# ShutdownLoop.net
KiCad netlist of a schematic drawn in Altium Designer
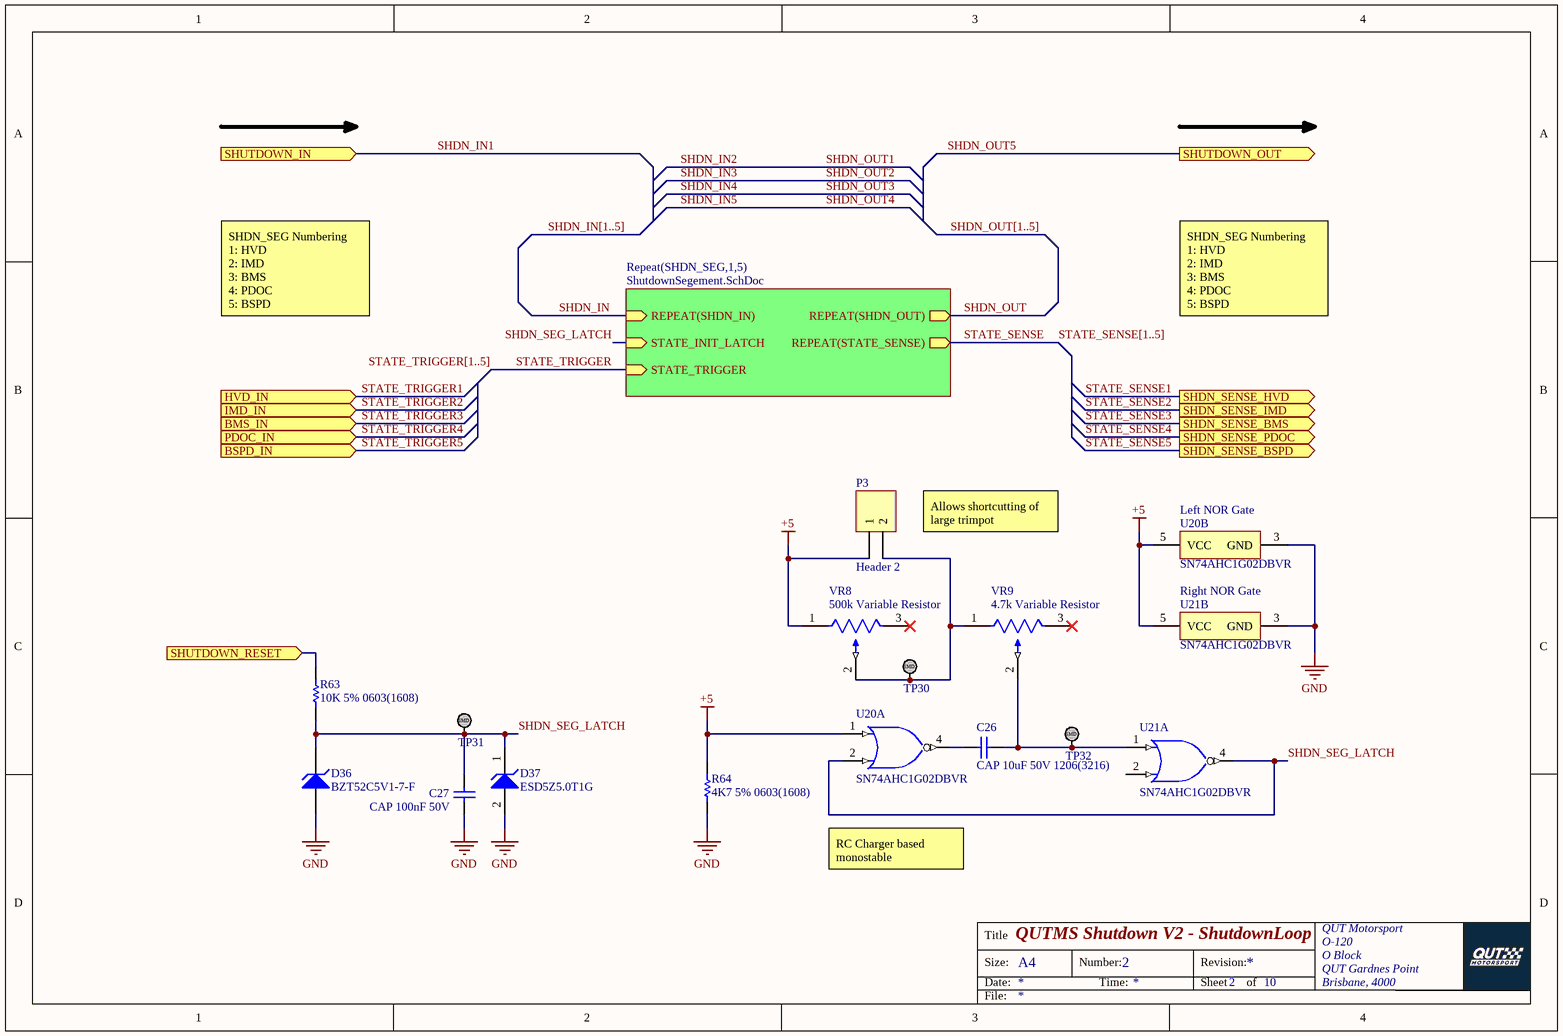
[diagram p0: ShutdownLoop.SchDoc]

(export (version "E")
  (design (tool "Eeschema 10.0.6"))
  (components
    (comp (ref "C26")
      (value "CAP 10uF 50V 1206(3216)")
      (footprint "CAPC1206(3216)190_M")
      (description "CAP 10uF 50V ±10% 1206 (3216 Metric) Thickness 1.9mm SMD")
      (fields (field (name "TOLERANCE") "Â±10%"))
      (libsource (lib "Altium Content Vault") (part "CAP"))
    )
    (comp (ref "C27")
      (value "CAP 100nF 50V")
      (footprint "CAPC0603(1608)100_L")
      (description "CAP 100nF 50V ±5% 0603 (1608 Metric) Thickness 1mm SMD")
      (fields (field (name "TOLERANCE") "Â±5%"))
      (libsource (lib "Altium Content Vault") (part "CAP"))
    )
    (comp (ref "D36")
      (value "BZT52C5V1-7-F")
      (footprint "DIOD-SOD123_V")
      (description "Surface Mount Zener Diode, 5.1 V, -65 to 150 degC, 2-Pin SMD (SOD-123), RoHS, Tape and Reel")
      (fields (field (name "MANUFACTURER") "DiodesIncorporated"))
      (libsource (lib "Altium Content Vault") (part "DZEN-AK-2"))
    )
    (comp (ref "D37")
      (value "ESD5Z5.0T1G")
      (footprint "ONSC-SOD-523-2-502-01_V")
      (fields (field (name "MANUFACTURER") "On Semiconductor"))
      (libsource (lib "Altium Content Vault") (part "ONSC-K1A2-2"))
    )
    (comp (ref "P3")
      (value "Header 2")
      (footprint "HDR1X2")
      (description "Header, 2-Pin")
      (fields (field (name "PUBLISHER") "Altium Limited"))
      (libsource (lib "Miscellaneous Connectors") (part "Header 2"))
    )
    (comp (ref "R63")
      (value "10K 5% 0603(1608)")
      (footprint "RESC0603(1608)_N")
      (description "10K 0.1W 5% 0603 (1608 Metric)  SMD")
      (fields (field (name "TOLERANCE") "5 %") (field (name "POWER") "0.1 W"))
      (libsource (lib "Altium Content Vault") (part "RES"))
    )
    (comp (ref "R64")
      (value "4K7 5% 0603(1608)")
      (footprint "RESC0603(1608)_N")
      (description "4K7 0.1W 5% 0603 (1608 Metric)  SMD")
      (fields (field (name "TOLERANCE") "5 %") (field (name "POWER") "0.1 W"))
      (libsource (lib "Altium Content Vault") (part "RES"))
    )
    (comp (ref "TP30")
      (value "TestPoint_SMD")
      (footprint "TestPointSMD")
      (libsource (lib "StandardTest") (part "TestPoint_SMD"))
    )
    (comp (ref "TP31")
      (value "TestPoint_SMD")
      (footprint "TestPointSMD")
      (libsource (lib "StandardTest") (part "TestPoint_SMD"))
    )
    (comp (ref "TP32")
      (value "TestPoint_SMD")
      (footprint "TestPointSMD")
      (libsource (lib "StandardTest") (part "TestPoint_SMD"))
    )
    (comp (ref "U20")
      (value "SN74AHC1G02DBVR")
      (footprint "DBV0005A_L")
      (description "Single 2-Input Positive-NOR Gate, DBV0005A, LARGE T&R")
      (fields
        (field (name "MANUFACTURER") "Texas Instruments")
        (field (name "GENERIC PART NUMBER") "SN74AHC1G02")
      )
      (libsource (lib "Altium Content Vault") (part "TI-SN74XXX1X02-5"))
    )
    (comp (ref "U21")
      (value "SN74AHC1G02DBVR")
      (footprint "DBV0005A_L")
      (description "Single 2-Input Positive-NOR Gate, DBV0005A, LARGE T&R")
      (fields
        (field (name "MANUFACTURER") "Texas Instruments")
        (field (name "GENERIC PART NUMBER") "SN74AHC1G02")
      )
      (libsource (lib "Altium Content Vault") (part "TI-SN74XXX1X02-5"))
    )
    (comp (ref "VR8")
      (value "500k Variable Resistor")
      (footprint "VG039NCHXTB472")
      (description "500K ±25% ±250 ppm/°C SMD Variable Resistors RoHS ¦ VG039NCHXTB504")
      (libsource (lib "QUTMS_PotentiometerLibrary") (part "500k Variable Resistor"))
    )
    (comp (ref "VR9")
      (value "4.7k Variable Resistor")
      (footprint "VG039NCHXTB472")
      (description "4k7 ±25% ±250 ppm/°C SMD Variable Resistors RoHS ¦ VG039NCHXTB472")
      (libsource (lib "QUTMS_PotentiometerLibrary") (part "4.7k Variable Resistor"))
    )
  )
  (nets
    (net (code "1") (name "+5") (class "Default")
      (node (ref "P3") (pin "1") (pinfunction "1_1") (pintype "passive"))
      (node (ref "R64") (pin "2") (pinfunction "2_2") (pintype "passive"))
      (node (ref "U20") (pin "1") (pinfunction "A_1") (pintype "input"))
      (node (ref "U20") (pin "5") (pinfunction "VCC_5") (pintype "power_in"))
      (node (ref "U21") (pin "5") (pinfunction "VCC_5") (pintype "power_in"))
      (node (ref "VR8") (pin "1") (pinfunction "48_1") (pintype "passive"))
    )
    (net (code "12") (name "/SHDN_SEG_LATCH") (class "Default")
      (node (ref "C27") (pin "1") (pinfunction "1_1") (pintype "passive"))
      (node (ref "D36") (pin "2") (pinfunction "K_2") (pintype "passive"))
      (node (ref "D37") (pin "1") (pinfunction "K_1") (pintype "passive"))
      (node (ref "R63") (pin "2") (pinfunction "2_2") (pintype "passive"))
      (node (ref "TP31") (pin "1") (pinfunction "1_1") (pintype "passive"))
      (node (ref "U20") (pin "2") (pinfunction "B_2") (pintype "input"))
      (node (ref "U21") (pin "4") (pinfunction "Y_4") (pintype "output"))
    )
    (net (code "13") (name "/SHUTDOWN_RESET") (class "Default")
      (node (ref "R63") (pin "1") (pinfunction "1_1") (pintype "passive"))
    )
    (net (code "28") (name "GND") (class "Default")
      (node (ref "C27") (pin "2") (pinfunction "2_2") (pintype "passive"))
      (node (ref "D36") (pin "1") (pinfunction "A_1") (pintype "passive"))
      (node (ref "D37") (pin "2") (pinfunction "A_2") (pintype "passive"))
      (node (ref "R64") (pin "1") (pinfunction "1_1") (pintype "passive"))
      (node (ref "U20") (pin "3") (pinfunction "GND_3") (pintype "power_in"))
      (node (ref "U21") (pin "3") (pinfunction "GND_3") (pintype "power_in"))
    )
    (net (code "29") (name "Net-(U20A-Y)") (class "Default")
      (node (ref "C26") (pin "2") (pinfunction "2_2") (pintype "passive"))
      (node (ref "U20") (pin "4") (pinfunction "Y_4") (pintype "output"))
    )
    (net (code "30") (name "Net-(U21A-A)") (class "Default")
      (node (ref "C26") (pin "1") (pinfunction "1_1") (pintype "passive"))
      (node (ref "TP32") (pin "1") (pinfunction "1_1") (pintype "passive"))
      (node (ref "U21") (pin "1") (pinfunction "A_1") (pintype "input"))
      (node (ref "VR9") (pin "2") (pinfunction "50_2") (pintype "output"))
    )
    (net (code "31") (name "Net-(VR8-50)") (class "Default")
      (node (ref "P3") (pin "2") (pinfunction "2_2") (pintype "passive"))
      (node (ref "TP30") (pin "1") (pinfunction "1_1") (pintype "passive"))
      (node (ref "VR8") (pin "2") (pinfunction "50_2") (pintype "output"))
      (node (ref "VR9") (pin "1") (pinfunction "48_1") (pintype "passive"))
    )
    (net (code "32") (name "unconnected-(U21A-B-Pad2)") (class "Default")
      (node (ref "U21") (pin "2") (pinfunction "B_2") (pintype "input"))
    )
    (net (code "33") (name "unconnected-(VR8-49-Pad3)") (class "Default")
      (node (ref "VR8") (pin "3") (pinfunction "49_3") (pintype "passive+no_connect"))
    )
    (net (code "34") (name "unconnected-(VR9-49-Pad3)") (class "Default")
      (node (ref "VR9") (pin "3") (pinfunction "49_3") (pintype "passive+no_connect"))
    )
  )
)
